# Sheet2.net
KiCad netlist of a schematic drawn in Altium Designer
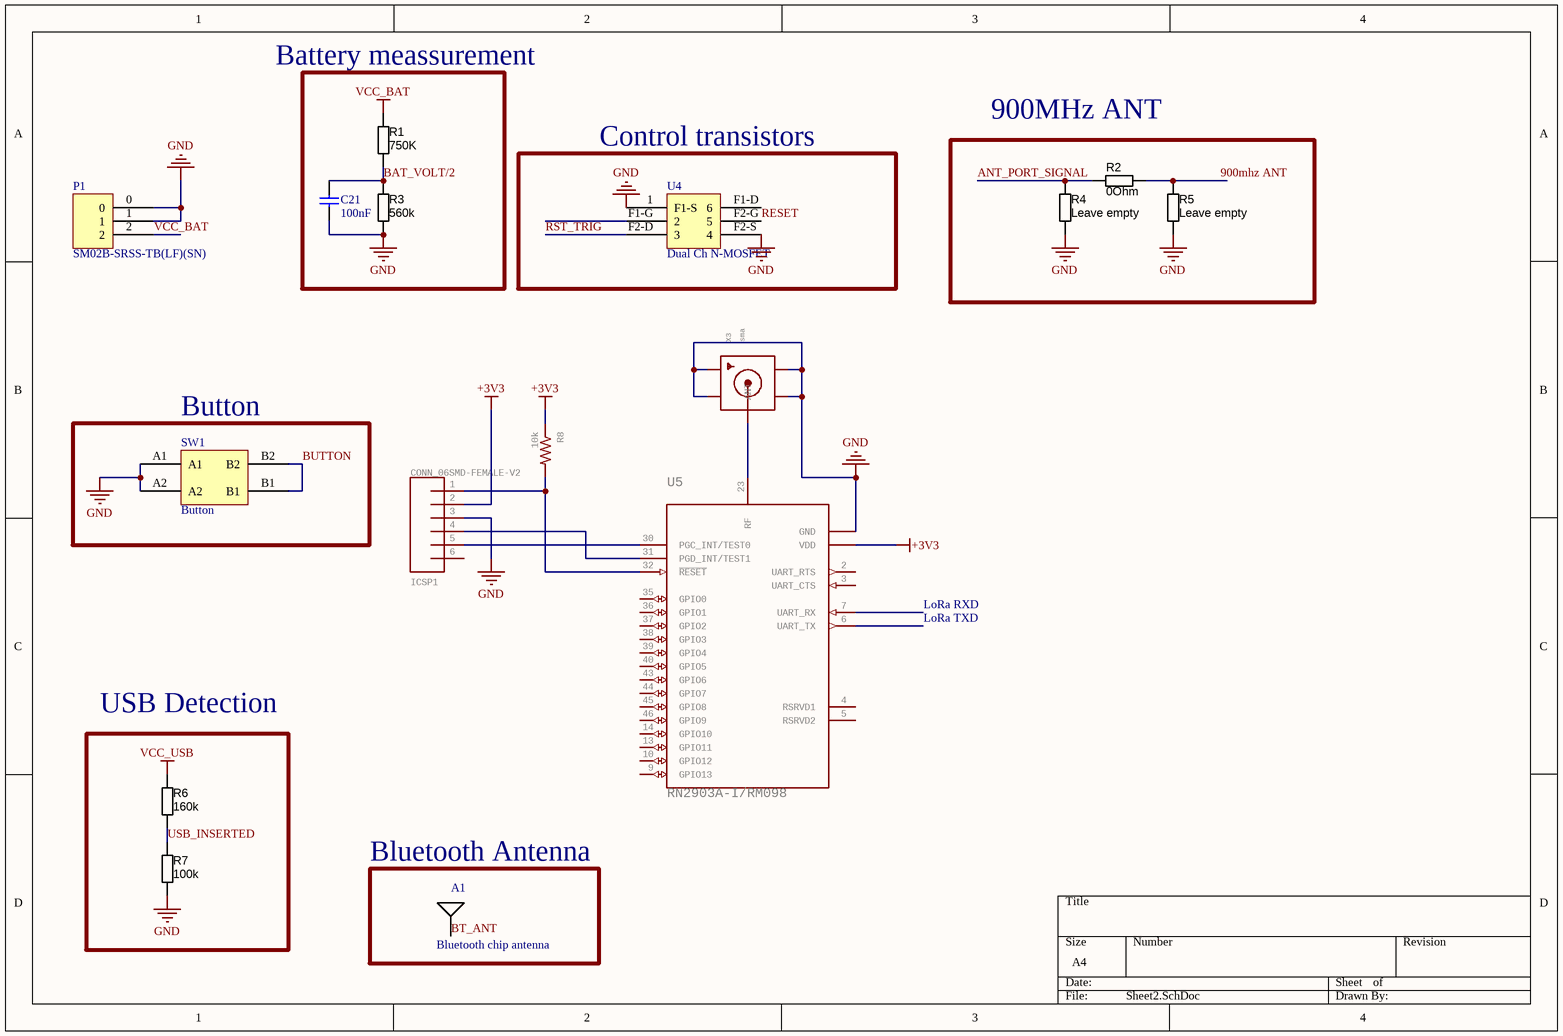
[diagram p0: Sheet2.SchDoc]

(export (version "E")
  (design (tool "Eeschema 10.0.6"))
  (components
    (comp (ref "A1")
      (value "Bluetooth chip antenna")
      (footprint "2450AT18A100E")
      (description "Antenna (2450AT18A100E)")
      (libsource (lib "Sarita SCHLib") (part "2450AT18A100E"))
    )
    (comp (ref "C21")
      (value "100nF")
      (footprint "CAPC1005X04L")
      (description "Generic 10%, X7R, 0402, Capacitor")
      (fields (field (name "PART NUMBER") "C0402-100n") (field (name "PUBLISHER") "Nordic Semiconductor"))
      (libsource (lib "Nordic Passive DB") (part "CAP"))
    )
    (comp (ref "ICSP1")
      (value "CONN_06SMD-FEMALE-V2")
      (footprint "1X06-SMD-FEMALE")
      (libsource (lib "SparkFun-Connectors") (part "CONN_06SMD-FEMALE-V2"))
    )
    (comp (ref "P1")
      (value "SM02B-SRSS-TB(LF)(SN)")
      (footprint "BM02B-SRSS-TB")
      (libsource (lib "Sarita CareTech Alitum SCH Lib V1") (part "SM02B-SRSS-TB(LF)(SN)"))
    )
    (comp (ref "R1")
      (value "750K")
      (footprint "RESC1005N")
      (description "Generic 1% 0402 resistor")
      (fields (field (name "TOLERANCE") "±5%") (field (name "Comment") "750K 1%"))
      (libsource (lib "PBL - Resistors") (part "RES_2K2_0402_5%"))
    )
    (comp (ref "R2")
      (value "0Ohm")
      (footprint "RESC1005N")
      (description "Resistor SMD  0402")
      (fields (field (name "TOLERANCE") "±5%"))
      (libsource (lib "PBL - Resistors") (part "RES_2K2_0402_5%"))
    )
    (comp (ref "R3")
      (value "560k")
      (footprint "RESC1005N")
      (description "Generic 1% 0402 resistor")
      (fields (field (name "TOLERANCE") "±5%") (field (name "Comment") "560K 1%"))
      (libsource (lib "PBL - Resistors") (part "RES_2K2_0402_5%"))
    )
    (comp (ref "R4")
      (value "Leave empty")
      (footprint "RESC1005N")
      (description "Resistor SMD 0402 (not mounted)")
      (fields (field (name "TOLERANCE") "±5%") (field (name "Comment") "not mounted"))
      (libsource (lib "") (part "RES_2K2_0402_5%_1"))
    )
    (comp (ref "R5")
      (value "Leave empty")
      (footprint "RESC1005N")
      (description "Resistor SMD  0402 (not mounted)")
      (fields (field (name "TOLERANCE") "±5%") (field (name "Comment") "not mounted"))
      (libsource (lib "") (part "RES_2K2_0402_5%_1"))
    )
    (comp (ref "R6")
      (value "160k")
      (footprint "RESC1005N")
      (description "Generic 5% 0402 resistor")
      (fields (field (name "TOLERANCE") "±5%"))
      (libsource (lib "PBL - Resistors") (part "RES_2K2_0402_5%"))
    )
    (comp (ref "R7")
      (value "100k")
      (footprint "RESC1005N")
      (description "Generic 5% 0402 resistor")
      (fields (field (name "TOLERANCE") "±5%"))
      (libsource (lib "PBL - Resistors") (part "RES_2K2_0402_5%"))
    )
    (comp (ref "R8")
      (value "10k")
      (footprint "R0603")
      (description "RESISTOR, American symbol")
      (libsource (lib "resistor") (part "R-US_R0603"))
    )
    (comp (ref "SW1")
      (value "Button")
      (footprint "EVQ-Q2K02W")
      (description "EVQ-Q2K03W")
      (libsource (lib "Sarita CareTech Alitum SCH Lib V1") (part "EVQ-Q2K02W"))
    )
    (comp (ref "U4")
      (value "Dual Ch N-MOSFET")
      (footprint "FC6946010R")
      (description "FC6946010R")
      (libsource (lib "Sarita CareTech Alitum SCH Lib V1") (part "FC6946010R"))
    )
    (comp (ref "U5")
      (value "RN2903A-I/RM098")
      (footprint "XCVR_RN2903A-I/RM098")
      (description "300kbps 18.5 dBm LoRa (Low Power Long Range) 915 MHz Transceiver Module")
      (fields (field (name "MF") "Microchip") (field (name "LIBRARYNAME") "bitsetters"))
      (libsource (lib "bitsetters") (part "RN2903A-I/RM098"))
    )
    (comp (ref "X3")
      (value "sma")
      (footprint "SMA_EDGELAUNCH")
      (description "SMA Connector   90Â° DIP SMA Connector, 50 Ohm (4UConnector: 07259)")
      (libsource (lib "adafruit") (part "SMACONNECTOR_EDGE"))
    )
  )
  (nets
    (net (code "1") (name "+3V3") (class "Default")
      (node (ref "ICSP1") (pin "2") (pinfunction "2_2") (pintype "passive"))
      (node (ref "R8") (pin "1") (pinfunction "1_1") (pintype "passive"))
      (node (ref "U5") (pin "12_34") (pinfunction "VDD_12_34") (pintype "power_in"))
    )
    (net (code "2") (name "/900mhz ANT") (class "Default")
      (node (ref "R2") (pin "2") (pinfunction "2_2") (pintype "passive"))
      (node (ref "R5") (pin "2") (pinfunction "2_2") (pintype "passive"))
    )
    (net (code "3") (name "/ANT_PORT_SIGNAL") (class "Default")
      (node (ref "R2") (pin "1") (pinfunction "1_1") (pintype "passive"))
      (node (ref "R4") (pin "2") (pinfunction "2_2") (pintype "passive"))
    )
    (net (code "4") (name "/BAT_VOLT{slash}2") (class "Default")
      (node (ref "C21") (pin "1") (pinfunction "1_1") (pintype "passive"))
      (node (ref "R1") (pin "1") (pinfunction "1_1") (pintype "passive"))
      (node (ref "R3") (pin "2") (pinfunction "2_2") (pintype "passive"))
    )
    (net (code "5") (name "/BT_ANT") (class "Default")
      (node (ref "A1") (pin "Feed") (pinfunction "Feed_Feed") (pintype "passive"))
    )
    (net (code "6") (name "/BUTTON") (class "Default")
      (node (ref "SW1") (pin "B1") (pinfunction "B1_B1") (pintype "passive"))
      (node (ref "SW1") (pin "B2") (pinfunction "B2_B2") (pintype "passive"))
    )
    (net (code "7") (name "/RESET") (class "Default")
      (node (ref "U4") (pin "F2-G") (pinfunction "5_F2-G") (pintype "passive"))
    )
    (net (code "8") (name "/RST_TRIG") (class "Default")
      (node (ref "U4") (pin "F2-D") (pinfunction "3_F2-D") (pintype "passive"))
    )
    (net (code "9") (name "/USB_INSERTED") (class "Default")
      (node (ref "R6") (pin "1") (pinfunction "1_1") (pintype "passive"))
      (node (ref "R7") (pin "2") (pinfunction "2_2") (pintype "passive"))
    )
    (net (code "10") (name "GND") (class "Default")
      (node (ref "C21") (pin "2") (pinfunction "2_2") (pintype "passive"))
      (node (ref "ICSP1") (pin "3") (pinfunction "3_3") (pintype "passive"))
      (node (ref "P1") (pin "0") (pinfunction "0_0") (pintype "passive"))
      (node (ref "P1") (pin "1") (pinfunction "1_1") (pintype "passive"))
      (node (ref "R3") (pin "1") (pinfunction "1_1") (pintype "passive"))
      (node (ref "R4") (pin "1") (pinfunction "1_1") (pintype "passive"))
      (node (ref "R5") (pin "1") (pinfunction "1_1") (pintype "passive"))
      (node (ref "R7") (pin "1") (pinfunction "1_1") (pintype "passive"))
      (node (ref "SW1") (pin "A1") (pinfunction "A1_A1") (pintype "passive"))
      (node (ref "SW1") (pin "A2") (pinfunction "A2_A2") (pintype "passive"))
      (node (ref "U4") (pin "1") (pinfunction "F1-S_1") (pintype "passive"))
      (node (ref "U4") (pin "F2-S") (pinfunction "4_F2-S") (pintype "passive"))
      (node (ref "U5") (pin "1_8_11_20_21_22_24_26_27_28_33_41_47") (pinfunction "GND_1_8_11_20_21_22_24_26_27_28_33_41_47") (pintype "power_in"))
      (node (ref "X3") (pin "GND@1") (pinfunction "GND4_GND@1") (pintype "power_in"))
      (node (ref "X3") (pin "GND@2") (pinfunction "GND3_GND@2") (pintype "power_in"))
      (node (ref "X3") (pin "GND@3") (pinfunction "GND2_GND@3") (pintype "power_in"))
      (node (ref "X3") (pin "GND@4") (pinfunction "GND1_GND@4") (pintype "power_in"))
    )
    (net (code "11") (name "Net-(U5-PGC_INT{slash}TEST0)") (class "Default")
      (node (ref "ICSP1") (pin "5") (pinfunction "5_5") (pintype "passive"))
      (node (ref "U5") (pin "30") (pinfunction "PGC_INT/TEST0_30") (pintype "passive"))
    )
    (net (code "12") (name "Net-(U5-PGD_INT{slash}TEST1)") (class "Default")
      (node (ref "ICSP1") (pin "4") (pinfunction "4_4") (pintype "passive"))
      (node (ref "U5") (pin "31") (pinfunction "PGD_INT/TEST1_31") (pintype "passive"))
    )
    (net (code "13") (name "Net-(U5-RF)") (class "Default")
      (node (ref "U5") (pin "23") (pinfunction "RF_23") (pintype "passive"))
      (node (ref "X3") (pin "P") (pinfunction "ANT_P") (pintype "bidirectional"))
    )
    (net (code "14") (name "Net-(U5-~{RESET})") (class "Default")
      (node (ref "ICSP1") (pin "1") (pinfunction "1_1") (pintype "passive"))
      (node (ref "R8") (pin "2") (pinfunction "2_2") (pintype "passive"))
      (node (ref "U5") (pin "32") (pinfunction "~{RESET}_32") (pintype "input"))
    )
    (net (code "15") (name "VCC_BAT") (class "Default")
      (node (ref "P1") (pin "2") (pinfunction "2_2") (pintype "passive"))
      (node (ref "R1") (pin "2") (pinfunction "2_2") (pintype "passive"))
    )
    (net (code "16") (name "VCC_USB") (class "Default")
      (node (ref "R6") (pin "2") (pinfunction "2_2") (pintype "passive"))
    )
    (net (code "17") (name "unconnected-(ICSP1-Pad6)") (class "Default")
      (node (ref "ICSP1") (pin "6") (pinfunction "6_6") (pintype "passive"))
    )
    (net (code "18") (name "unconnected-(U4-2-PadF1-G)") (class "Default")
      (node (ref "U4") (pin "F1-G") (pinfunction "2_F1-G") (pintype "passive"))
    )
    (net (code "19") (name "unconnected-(U4-6-PadF1-D)") (class "Default")
      (node (ref "U4") (pin "F1-D") (pinfunction "6_F1-D") (pintype "passive"))
    )
    (net (code "20") (name "unconnected-(U5-GPIO0-Pad35)") (class "Default")
      (node (ref "U5") (pin "35") (pinfunction "GPIO0_35") (pintype "bidirectional"))
    )
    (net (code "21") (name "unconnected-(U5-GPIO1-Pad36)") (class "Default")
      (node (ref "U5") (pin "36") (pinfunction "GPIO1_36") (pintype "bidirectional"))
    )
    (net (code "22") (name "unconnected-(U5-GPIO2-Pad37)") (class "Default")
      (node (ref "U5") (pin "37") (pinfunction "GPIO2_37") (pintype "bidirectional"))
    )
    (net (code "23") (name "unconnected-(U5-GPIO3-Pad38)") (class "Default")
      (node (ref "U5") (pin "38") (pinfunction "GPIO3_38") (pintype "bidirectional"))
    )
    (net (code "24") (name "unconnected-(U5-GPIO4-Pad39)") (class "Default")
      (node (ref "U5") (pin "39") (pinfunction "GPIO4_39") (pintype "bidirectional"))
    )
    (net (code "25") (name "unconnected-(U5-GPIO5-Pad40)") (class "Default")
      (node (ref "U5") (pin "40") (pinfunction "GPIO5_40") (pintype "bidirectional"))
    )
    (net (code "26") (name "unconnected-(U5-GPIO6-Pad43)") (class "Default")
      (node (ref "U5") (pin "43") (pinfunction "GPIO6_43") (pintype "bidirectional"))
    )
    (net (code "27") (name "unconnected-(U5-GPIO7-Pad44)") (class "Default")
      (node (ref "U5") (pin "44") (pinfunction "GPIO7_44") (pintype "bidirectional"))
    )
    (net (code "28") (name "unconnected-(U5-GPIO8-Pad45)") (class "Default")
      (node (ref "U5") (pin "45") (pinfunction "GPIO8_45") (pintype "bidirectional"))
    )
    (net (code "29") (name "unconnected-(U5-GPIO9-Pad46)") (class "Default")
      (node (ref "U5") (pin "46") (pinfunction "GPIO9_46") (pintype "bidirectional"))
    )
    (net (code "30") (name "unconnected-(U5-GPIO10-Pad14)") (class "Default")
      (node (ref "U5") (pin "14") (pinfunction "GPIO10_14") (pintype "bidirectional"))
    )
    (net (code "31") (name "unconnected-(U5-GPIO11-Pad13)") (class "Default")
      (node (ref "U5") (pin "13") (pinfunction "GPIO11_13") (pintype "bidirectional"))
    )
    (net (code "32") (name "unconnected-(U5-GPIO12-Pad10)") (class "Default")
      (node (ref "U5") (pin "10") (pinfunction "GPIO12_10") (pintype "bidirectional"))
    )
    (net (code "33") (name "unconnected-(U5-GPIO13-Pad9)") (class "Default")
      (node (ref "U5") (pin "9") (pinfunction "GPIO13_9") (pintype "bidirectional"))
    )
    (net (code "34") (name "unconnected-(U5-RSRVD1-Pad4)") (class "Default")
      (node (ref "U5") (pin "4") (pinfunction "RSRVD1_4") (pintype "passive"))
    )
    (net (code "35") (name "unconnected-(U5-RSRVD2-Pad5)") (class "Default")
      (node (ref "U5") (pin "5") (pinfunction "RSRVD2_5") (pintype "passive"))
    )
    (net (code "36") (name "unconnected-(U5-UART_CTS-Pad3)") (class "Default")
      (node (ref "U5") (pin "3") (pinfunction "UART_CTS_3") (pintype "input"))
    )
    (net (code "37") (name "unconnected-(U5-UART_RTS-Pad2)") (class "Default")
      (node (ref "U5") (pin "2") (pinfunction "UART_RTS_2") (pintype "output"))
    )
    (net (code "38") (name "unconnected-(U5-UART_RX-Pad7)") (class "Default")
      (node (ref "U5") (pin "7") (pinfunction "UART_RX_7") (pintype "input"))
    )
    (net (code "39") (name "unconnected-(U5-UART_TX-Pad6)") (class "Default")
      (node (ref "U5") (pin "6") (pinfunction "UART_TX_6") (pintype "output"))
    )
  )
)
